# Motor_-_Motor_Control.net
KiCad netlist of a schematic drawn in Altium Designer
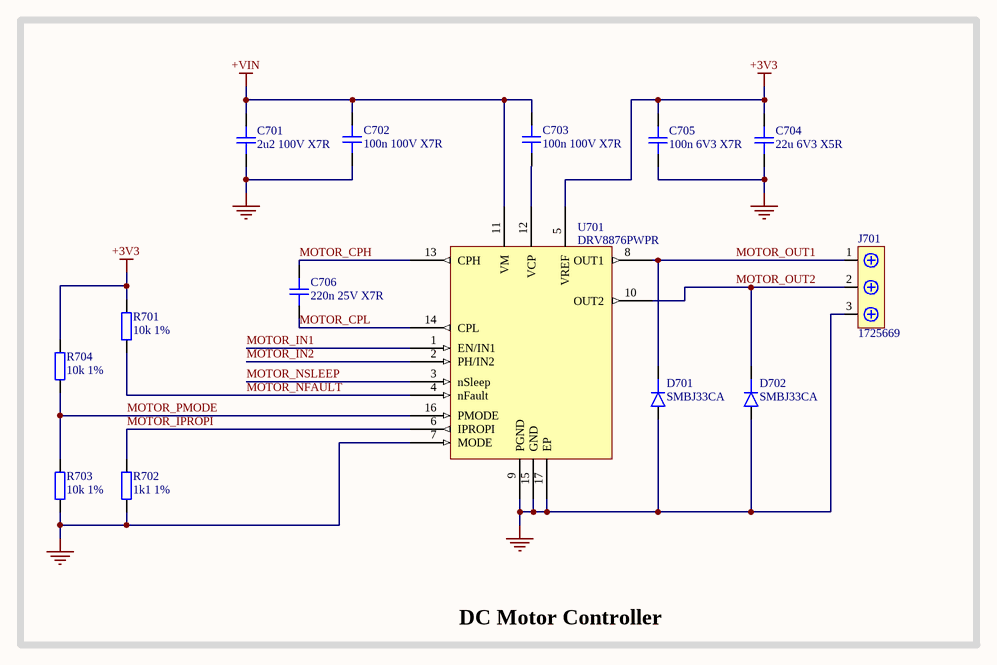
[diagram p0: Motor - Motor Control.SchDoc]

(export (version "E")
  (design (tool "Eeschema 10.0.6"))
  (components
    (comp (ref "C701")
      (value "2u2 100V X7R")
      (footprint "CAP_0805")
      (description "Capacitor SMD 0805")
      (libsource (lib "Schematic-Lib") (part "CAP_0805"))
    )
    (comp (ref "C702")
      (value "100n 100V X7R")
      (footprint "CAP_0603")
      (description "Capacitor SMD 0603")
      (libsource (lib "Schematic-Lib") (part "CAP_0603"))
    )
    (comp (ref "C703")
      (value "100n 100V X7R")
      (footprint "CAP_0603")
      (description "Capacitor SMD 0603")
      (libsource (lib "Schematic-Lib") (part "CAP_0603"))
    )
    (comp (ref "C704")
      (value "22u 6V3 X5R")
      (footprint "CAP_0603")
      (description "Capacitor SMD 0603")
      (fields
        (field (name "MANUFACTURER") "Samsung Electro-Mechanics")
        (field (name "MANUFACTURER PART NUMBER") "CL10A226MQ8NRNC")
      )
      (libsource (lib "Schematic-Lib") (part "CAP_0603"))
    )
    (comp (ref "C705")
      (value "100n 6V3 X7R")
      (footprint "CAP_0402")
      (description "Capacitor SMD 0402")
      (fields
        (field (name "MANUFACTURER") "YAGEO")
        (field (name "MANUFACTURER PART NUMBER") "CC0402KRX7R5BB104")
      )
      (libsource (lib "Schematic-Lib") (part "CAP_0402"))
    )
    (comp (ref "C706")
      (value "220n 25V X7R")
      (footprint "CAP_0603")
      (description "Capacitor SMD 0603")
      (fields
        (field (name "MANUFACTURER") "Samsung Electro-Mechanics")
        (field (name "MANUFACTURER PART NUMBER") "CL10A226MQ8NRNC")
      )
      (libsource (lib "Schematic-Lib") (part "CAP_0603"))
    )
    (comp (ref "D701")
      (value "SMBJ33CA")
      (footprint "DO-214AC-2 (SMA)")
      (description "Diode SMD SMA (DO-214AA)")
      (fields (field (name "MANUFACTURER") "Littelfuse"))
      (libsource (lib "Schematic-Lib") (part "D_SMA"))
    )
    (comp (ref "D702")
      (value "SMBJ33CA")
      (footprint "DO-214AC-2 (SMA)")
      (description "Diode SMD SMA (DO-214AA)")
      (fields (field (name "MANUFACTURER") "Littelfuse"))
      (libsource (lib "Schematic-Lib") (part "D_SMA"))
    )
    (comp (ref "J701")
      (value "1725669")
      (footprint "1725669")
      (description "Screw Terminal Block 3 Positions 2.54mm")
      (fields (field (name "MANUFACTURER") "Phoenix"))
      (libsource (lib "Schematic-Lib") (part "1725669"))
    )
    (comp (ref "R701")
      (value "10k 1%")
      (footprint "RES_0402")
      (description "Resistor SMD 0402")
      (fields
        (field (name "MANUFACTURER") "PANASONIC")
        (field (name "MANUFACTURER PART NUMBER") "ERJPA2F1002X")
      )
      (libsource (lib "Schematic-Lib-PhilsLab") (part "RES_0402"))
    )
    (comp (ref "R702")
      (value "1k1 1%")
      (footprint "RES_0402")
      (description "Resistor SMD 0402")
      (fields
        (field (name "MANUFACTURER") "PANASONIC")
        (field (name "MANUFACTURER PART NUMBER") "ERJPA2F1002X")
      )
      (libsource (lib "Schematic-Lib-PhilsLab") (part "RES_0402"))
    )
    (comp (ref "R703")
      (value "10k 1%")
      (footprint "RES_0402")
      (description "Resistor SMD 0402")
      (fields
        (field (name "MANUFACTURER") "PANASONIC")
        (field (name "MANUFACTURER PART NUMBER") "ERJPA2F1002X")
      )
      (libsource (lib "Schematic-Lib-PhilsLab") (part "RES_0402"))
    )
    (comp (ref "R704")
      (value "10k 1%")
      (footprint "RES_0402")
      (description "Resistor SMD 0402")
      (fields
        (field (name "MANUFACTURER") "PANASONIC")
        (field (name "MANUFACTURER PART NUMBER") "ERJPA2F1002X")
      )
      (libsource (lib "Schematic-Lib-PhilsLab") (part "RES_0402"))
    )
    (comp (ref "U701")
      (value "DRV8876PWPR")
      (footprint "SOP65P640X120-16N")
      (description "DRV8876 H-Bridge Motor Driver With Integrated Current Sense and Regulation")
      (fields (field (name "MANUFACTURER") "Texas Instruments"))
      (libsource (lib "Schematic-Lib") (part "DRV8876PWPR"))
    )
  )
  (nets
    (net (code "1") (name "+3V3") (class "Default")
      (node (ref "C704") (pin "2") (pinfunction "2_2") (pintype "passive"))
      (node (ref "C705") (pin "2") (pinfunction "2_2") (pintype "passive"))
      (node (ref "R701") (pin "2") (pinfunction "2_2") (pintype "passive"))
      (node (ref "R704") (pin "2") (pinfunction "2_2") (pintype "passive"))
      (node (ref "U701") (pin "5") (pinfunction "VREF_5") (pintype "power_in"))
    )
    (net (code "2") (name "+VIN") (class "Default")
      (node (ref "C701") (pin "2") (pinfunction "2_2") (pintype "passive"))
      (node (ref "C702") (pin "2") (pinfunction "2_2") (pintype "passive"))
      (node (ref "C703") (pin "2") (pinfunction "2_2") (pintype "passive"))
      (node (ref "U701") (pin "11") (pinfunction "VM_11") (pintype "power_in"))
    )
    (net (code "3") (name "/MOTOR_CPH") (class "Default")
      (node (ref "C706") (pin "2") (pinfunction "2_2") (pintype "passive"))
      (node (ref "U701") (pin "13") (pinfunction "CPH_13") (pintype "output"))
    )
    (net (code "4") (name "/MOTOR_CPL") (class "Default")
      (node (ref "C706") (pin "1") (pinfunction "1_1") (pintype "passive"))
      (node (ref "U701") (pin "14") (pinfunction "CPL_14") (pintype "output"))
    )
    (net (code "5") (name "/MOTOR_IN1") (class "Default")
      (node (ref "U701") (pin "1") (pinfunction "EN/IN1_1") (pintype "input"))
    )
    (net (code "6") (name "/MOTOR_IN2") (class "Default")
      (node (ref "U701") (pin "2") (pinfunction "PH/IN2_2") (pintype "input"))
    )
    (net (code "7") (name "/MOTOR_IPROPI") (class "Default")
      (node (ref "R702") (pin "2") (pinfunction "2_2") (pintype "passive"))
      (node (ref "U701") (pin "6") (pinfunction "IPROPI_6") (pintype "output"))
    )
    (net (code "8") (name "/MOTOR_NFAULT") (class "Default")
      (node (ref "R701") (pin "1") (pinfunction "1_1") (pintype "passive"))
      (node (ref "U701") (pin "4") (pinfunction "nFault_4") (pintype "input"))
    )
    (net (code "9") (name "/MOTOR_NSLEEP") (class "Default")
      (node (ref "U701") (pin "3") (pinfunction "nSleep_3") (pintype "input"))
    )
    (net (code "10") (name "/MOTOR_OUT1") (class "Default")
      (node (ref "D701") (pin "K") (pinfunction "K_K") (pintype "passive"))
      (node (ref "J701") (pin "1") (pinfunction "1_1") (pintype "passive"))
      (node (ref "U701") (pin "8") (pinfunction "OUT1_8") (pintype "output"))
    )
    (net (code "11") (name "/MOTOR_OUT2") (class "Default")
      (node (ref "D702") (pin "K") (pinfunction "K_K") (pintype "passive"))
      (node (ref "J701") (pin "2") (pinfunction "2_2") (pintype "passive"))
      (node (ref "U701") (pin "10") (pinfunction "OUT2_10") (pintype "output"))
    )
    (net (code "12") (name "/MOTOR_PMODE") (class "Default")
      (node (ref "R703") (pin "2") (pinfunction "2_2") (pintype "passive"))
      (node (ref "R704") (pin "1") (pinfunction "1_1") (pintype "passive"))
      (node (ref "U701") (pin "16") (pinfunction "PMODE_16") (pintype "input"))
    )
    (net (code "13") (name "GND") (class "Default")
      (node (ref "C701") (pin "1") (pinfunction "1_1") (pintype "passive"))
      (node (ref "C702") (pin "1") (pinfunction "1_1") (pintype "passive"))
      (node (ref "C704") (pin "1") (pinfunction "1_1") (pintype "passive"))
      (node (ref "C705") (pin "1") (pinfunction "1_1") (pintype "passive"))
      (node (ref "D701") (pin "A") (pinfunction "A_A") (pintype "passive"))
      (node (ref "D702") (pin "A") (pinfunction "A_A") (pintype "passive"))
      (node (ref "J701") (pin "3") (pinfunction "3_3") (pintype "passive"))
      (node (ref "R702") (pin "1") (pinfunction "1_1") (pintype "passive"))
      (node (ref "R703") (pin "1") (pinfunction "1_1") (pintype "passive"))
      (node (ref "U701") (pin "15") (pinfunction "GND_15") (pintype "passive"))
      (node (ref "U701") (pin "17") (pinfunction "EP_17") (pintype "passive"))
      (node (ref "U701") (pin "7") (pinfunction "MODE_7") (pintype "input"))
      (node (ref "U701") (pin "9") (pinfunction "PGND_9") (pintype "passive"))
    )
    (net (code "14") (name "Net-(U701-VCP)") (class "Default")
      (node (ref "C703") (pin "1") (pinfunction "1_1") (pintype "passive"))
      (node (ref "U701") (pin "12") (pinfunction "VCP_12") (pintype "power_in"))
    )
  )
)
